# SCH_night-light_2024-06-19.net
KiCad netlist of a schematic drawn in EasyEDA
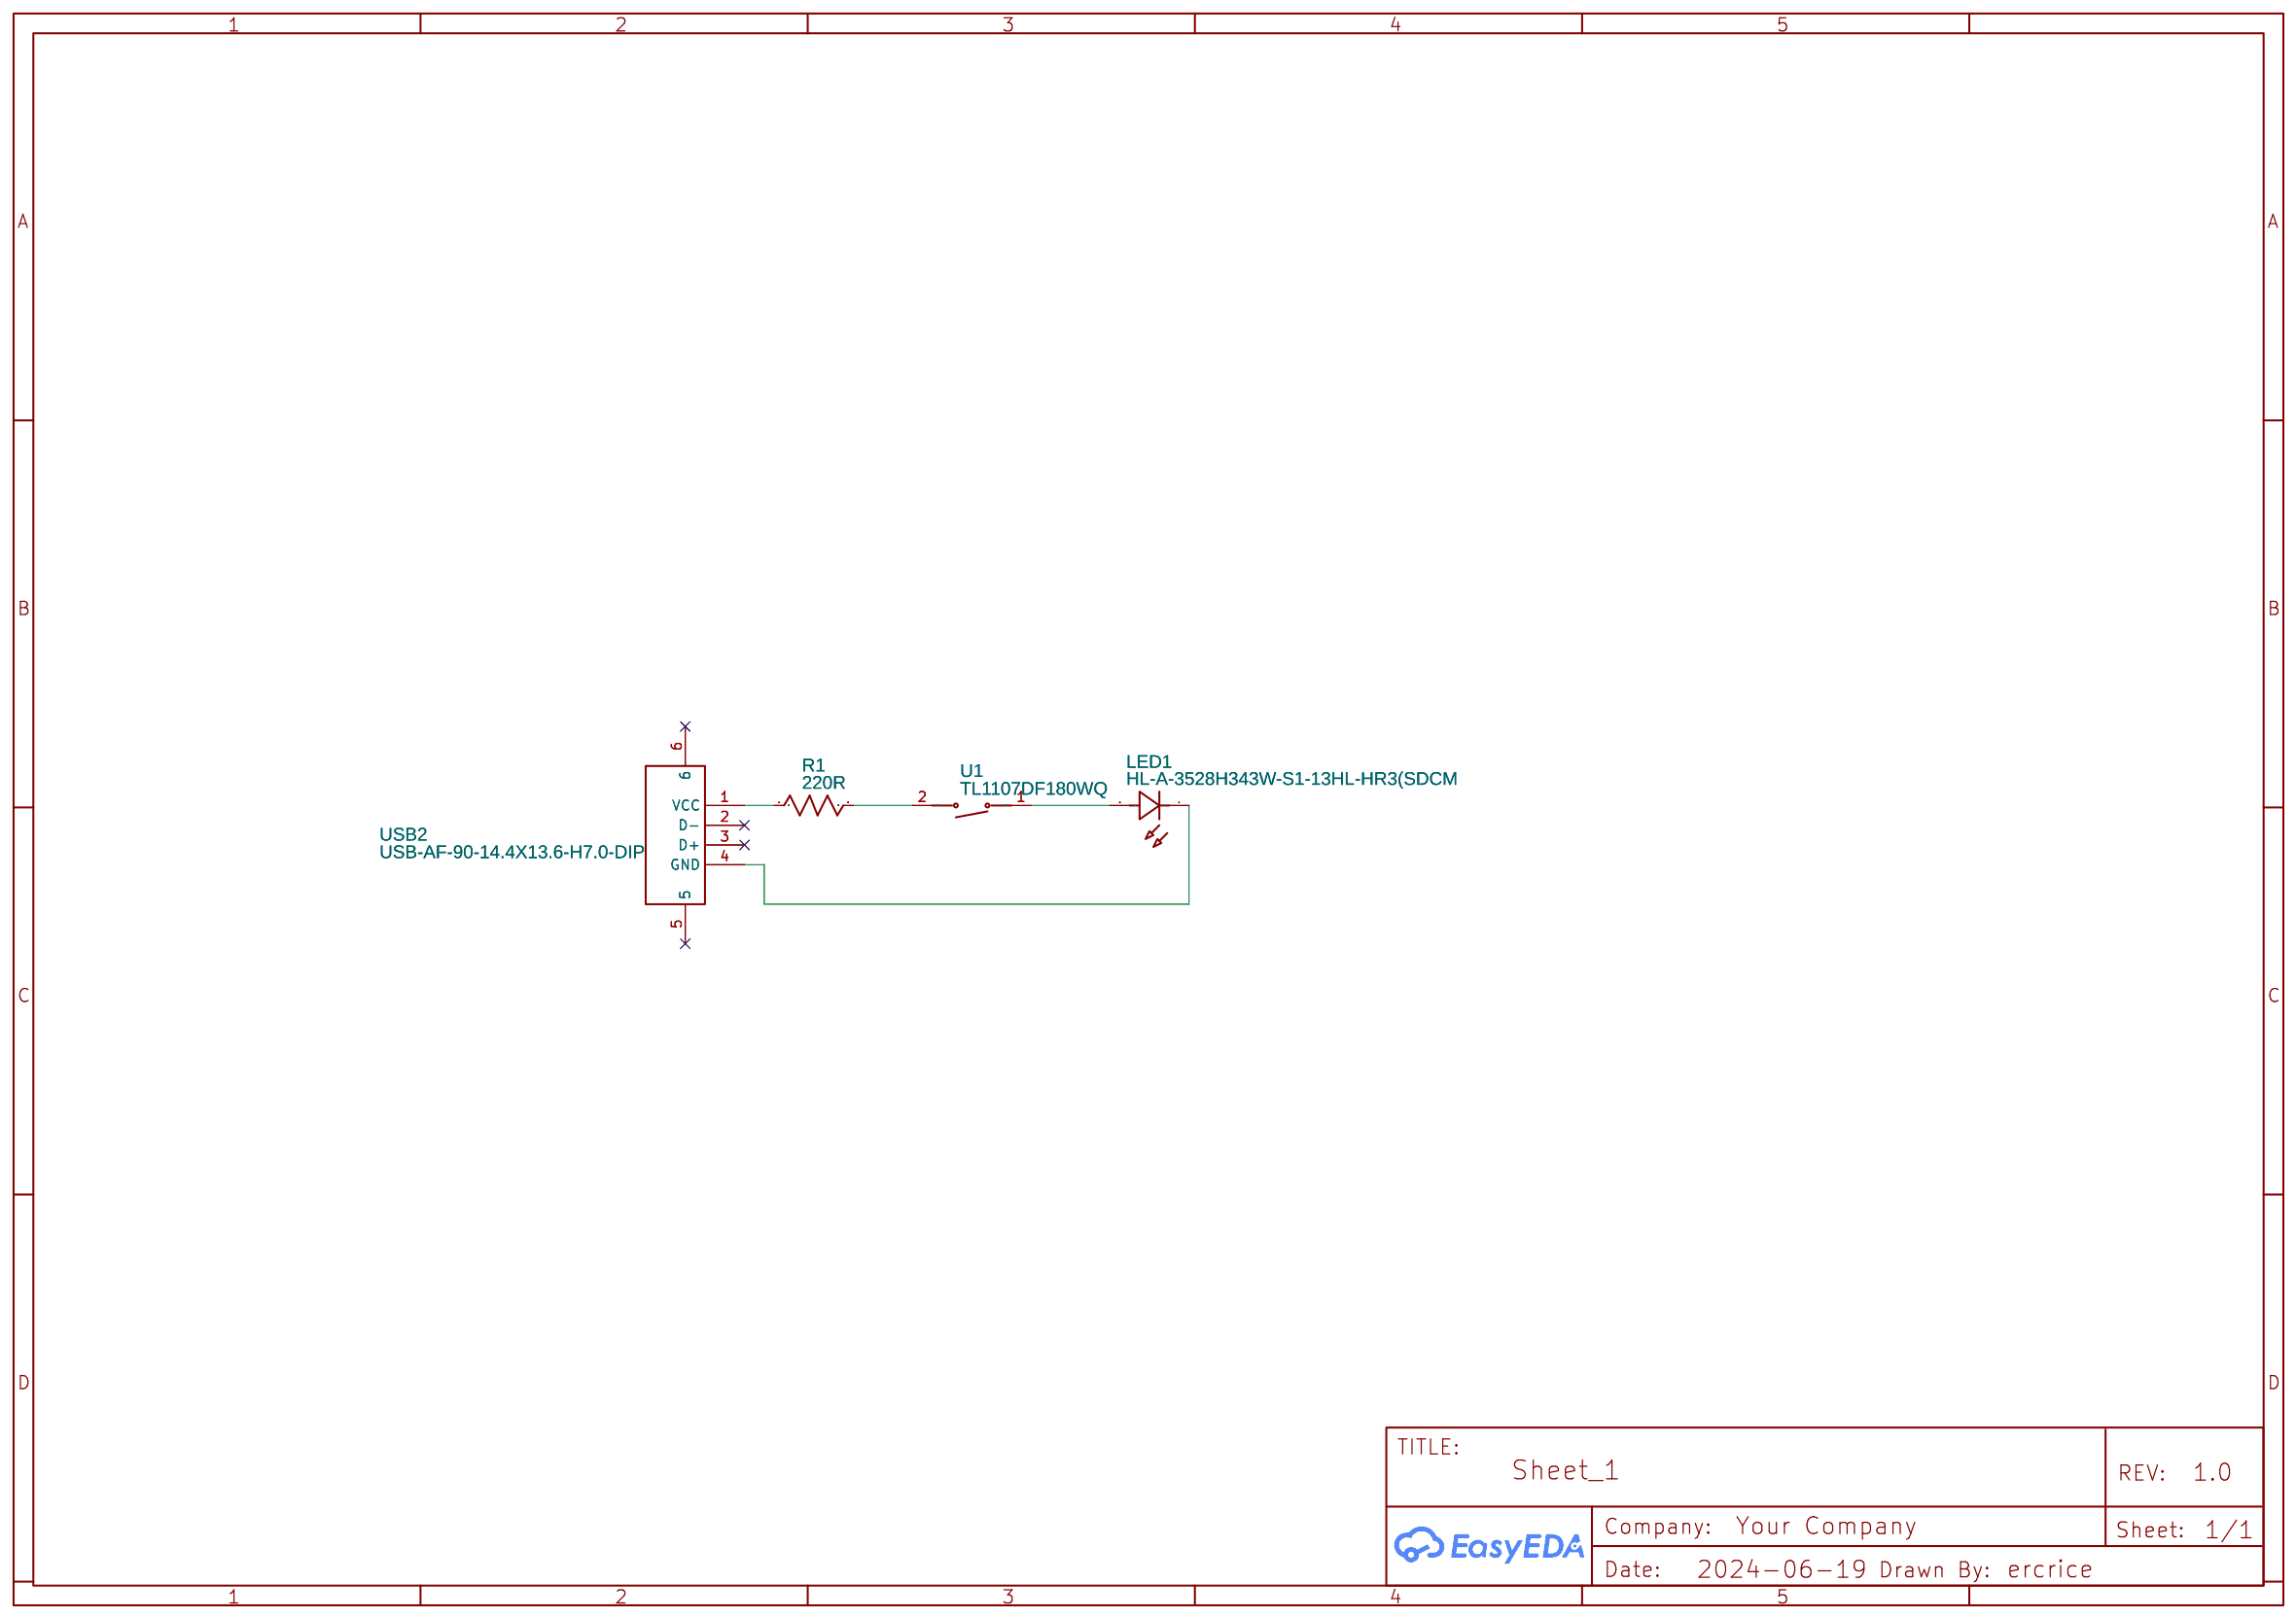
[diagram p0: schematic sheet]

(export (version "E")
  (design (tool "Eeschema 10.0.6"))
  (components
    (comp (ref "LED1")
      (value "HL-A-3528H343W-S1-13HL-HR3(SDCM")
      (fields
        (field (name "Manufacturer Part") "HL-A-3528H343W-S1-13HL-HR3(SDCM<6)(4750K-5300K)")
        (field (name "Manufacturer") "HONGLITRONIC(鸿利光电)")
      )
      (libsource (lib "") (part "HL-A-3528H343W-S1-13HL-HR3(SDCM"))
    )
    (comp (ref "R1") (value "220R") (libsource (lib "") (part "R_0603_US")))
    (comp (ref "U1")
      (value "TL1107DF180WQ")
      (fields (field (name "Manufacturer") "E-Switch"))
      (libsource (lib "") (part "TL1107DF180WQ"))
    )
    (comp (ref "USB2")
      (value "USB-AF-90-14.4X13.6-H7.0-DIP")
      (fields (field (name "Manufacturer Part") "903-131A1011D10100") (field (name "Manufacturer") "精拓金"))
      (libsource (lib "") (part "USB-AF-90-14.4X13.6-H7.0-DIP"))
    )
  )
  (nets
    (net (code "1") (name "Net-(LED1-A)") (class "Default")
      (node (ref "LED1") (pin "2") (pinfunction "A_2") (pintype "unspecified"))
      (node (ref "U1") (pin "1") (pinfunction "1_1") (pintype "unspecified"))
    )
    (net (code "2") (name "Net-(LED1-K)") (class "Default")
      (node (ref "LED1") (pin "1") (pinfunction "K_1") (pintype "unspecified"))
      (node (ref "USB2") (pin "4") (pinfunction "GND_4") (pintype "unspecified"))
    )
    (net (code "3") (name "Net-(R1-Pad2)") (class "Default")
      (node (ref "R1") (pin "2") (pinfunction "2_2") (pintype "unspecified"))
      (node (ref "U1") (pin "2") (pinfunction "2_2") (pintype "unspecified"))
    )
    (net (code "4") (name "Net-(USB2-VCC)") (class "Default")
      (node (ref "R1") (pin "1") (pinfunction "1_1") (pintype "unspecified"))
      (node (ref "USB2") (pin "1") (pinfunction "VCC_1") (pintype "unspecified"))
    )
    (net (code "5") (name "unconnected-(USB2-D+-Pad3)") (class "Default")
      (node (ref "USB2") (pin "3") (pinfunction "D+_3") (pintype "unspecified+no_connect"))
    )
    (net (code "6") (name "unconnected-(USB2-D--Pad2)") (class "Default")
      (node (ref "USB2") (pin "2") (pinfunction "D-_2") (pintype "unspecified+no_connect"))
    )
    (net (code "7") (name "unconnected-(USB2-Pad5)") (class "Default")
      (node (ref "USB2") (pin "5") (pinfunction "5_5") (pintype "unspecified+no_connect"))
    )
    (net (code "8") (name "unconnected-(USB2-Pad6)") (class "Default")
      (node (ref "USB2") (pin "6") (pinfunction "6_6") (pintype "unspecified+no_connect"))
    )
  )
)
